# RFM232_V02.net
KiCad netlist of a schematic drawn in Altium Designer
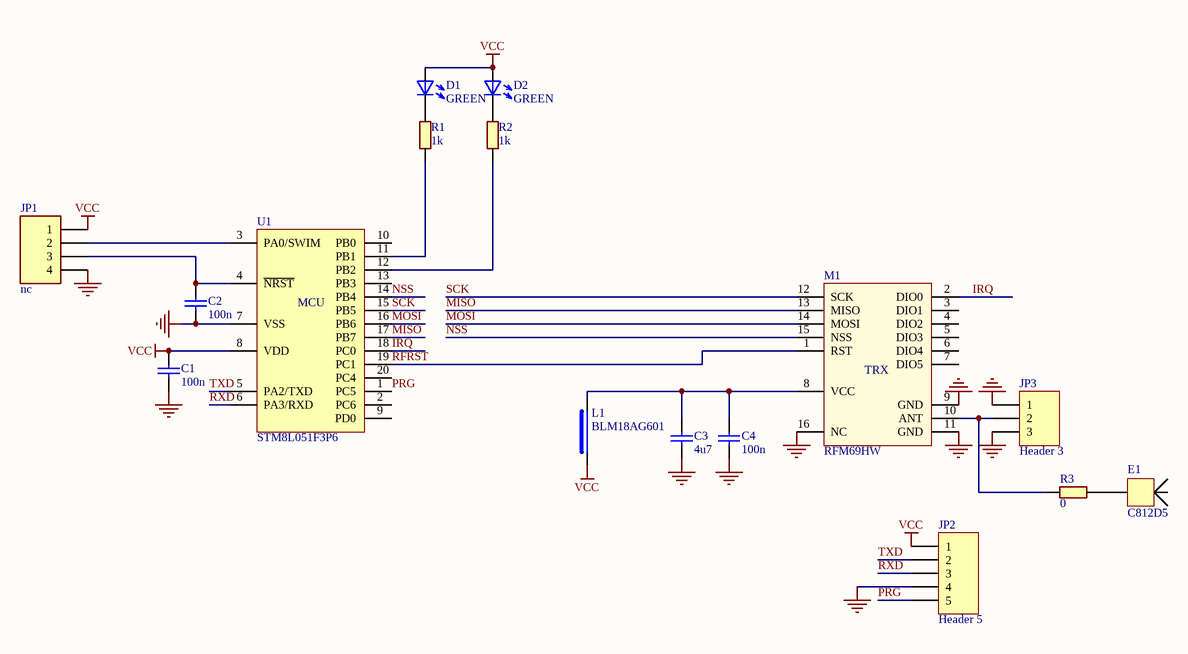
[diagram p0: RFM232_V02.SchDoc]

(export (version "E")
  (design (tool "Eeschema 10.0.6"))
  (components
    (comp (ref "C1") (value "100n") (footprint "CAPC1608X08N") (libsource (lib "Discrete") (part "CAPN")))
    (comp (ref "C2") (value "100n") (footprint "CAPC1608X08N") (libsource (lib "Discrete") (part "CAPN")))
    (comp (ref "C3") (value "4u7") (footprint "CAPC2012X11N") (libsource (lib "Discrete") (part "CAPN")))
    (comp (ref "C4") (value "100n") (footprint "CAPC1608X08N") (libsource (lib "Discrete") (part "CAPN")))
    (comp (ref "D1")
      (value "GREEN")
      (footprint "LEDC200X125X80L40N")
      (libsource (lib "Discrete") (part "DLED"))
    )
    (comp (ref "D2")
      (value "GREEN")
      (footprint "LEDC200X125X80L40N")
      (libsource (lib "Discrete") (part "DLED"))
    )
    (comp (ref "E1") (value "C812D5") (footprint "C812D5") (libsource (lib "RFUART") (part "C812D5")))
    (comp (ref "JP1")
      (value "nc")
      (footprint "HDRV4W70P254_4X1_889X254H754")
      (description "4 Pin Header 2,0 mm, 1x04")
      (libsource (lib "e4") (part "HEADER 4"))
    )
    (comp (ref "JP2")
      (value "Header 5")
      (footprint "HDRV5W70P254_5X1_1143X254H754")
      (description "Header, 5-Pin")
      (fields (field (name "PUBLISHER") "Altium Limited"))
      (libsource (lib "Miscellaneous Connectors") (part "Header 5"))
    )
    (comp (ref "JP3")
      (value "Header 3")
      (footprint "HDRV3W70P254_3X1_635X254H754")
      (description "Header, 3-Pin")
      (fields (field (name "PUBLISHER") "Altium Limited"))
      (libsource (lib "Miscellaneous Connectors") (part "Header 3"))
    )
    (comp (ref "L1")
      (value "BLM18AG601")
      (footprint "INDC1608X10N")
      (libsource (lib "Discrete") (part "SUPRESOR"))
    )
    (comp (ref "M1")
      (value "RFM69HW")
      (footprint "LGA16_RFM69")
      (libsource (lib "CLAP_M505_WL_BP_V22") (part "RFM69HW_V13_2"))
    )
    (comp (ref "R1") (value "1k") (footprint "RESC1608X06N") (libsource (lib "") (part "RES_1")))
    (comp (ref "R2") (value "1k") (footprint "RESC1608X06N") (libsource (lib "") (part "RES_1")))
    (comp (ref "R3") (value "0") (footprint "RESC2012X07N") (libsource (lib "Discrete") (part "RES")))
    (comp (ref "U1")
      (value "STM8L051F3P6")
      (footprint "TSOP65P640X110-20N")
      (libsource (lib "reedswitch_stm8l") (part "STM8L051F3P6"))
    )
  )
  (nets
    (net (code "1") (name "/IRQ") (class "Default")
      (node (ref "M1") (pin "2") (pinfunction "DIO0_2") (pintype "passive"))
      (node (ref "U1") (pin "18") (pinfunction "PC0_18") (pintype "passive"))
    )
    (net (code "2") (name "/MISO") (class "Default")
      (node (ref "M1") (pin "13") (pinfunction "MISO_13") (pintype "passive"))
      (node (ref "U1") (pin "17") (pinfunction "PB7_17") (pintype "passive"))
    )
    (net (code "3") (name "/MOSI") (class "Default")
      (node (ref "M1") (pin "14") (pinfunction "MOSI_14") (pintype "passive"))
      (node (ref "U1") (pin "16") (pinfunction "PB6_16") (pintype "passive"))
    )
    (net (code "4") (name "/NSS") (class "Default")
      (node (ref "M1") (pin "15") (pinfunction "NSS_15") (pintype "passive"))
      (node (ref "U1") (pin "14") (pinfunction "PB4_14") (pintype "passive"))
    )
    (net (code "5") (name "/PRG") (class "Default")
      (node (ref "JP2") (pin "5") (pinfunction "5_5") (pintype "passive"))
      (node (ref "U1") (pin "1") (pinfunction "PC5_1") (pintype "passive"))
    )
    (net (code "6") (name "/RFRST") (class "Default")
      (node (ref "M1") (pin "1") (pinfunction "RST_1") (pintype "passive"))
      (node (ref "U1") (pin "19") (pinfunction "PC1_19") (pintype "passive"))
    )
    (net (code "7") (name "/RXD") (class "Default")
      (node (ref "JP2") (pin "3") (pinfunction "3_3") (pintype "passive"))
      (node (ref "U1") (pin "6") (pinfunction "PA3/RXD_6") (pintype "passive"))
    )
    (net (code "8") (name "/SCK") (class "Default")
      (node (ref "M1") (pin "12") (pinfunction "SCK_12") (pintype "passive"))
      (node (ref "U1") (pin "15") (pinfunction "PB5_15") (pintype "passive"))
    )
    (net (code "9") (name "/TXD") (class "Default")
      (node (ref "JP2") (pin "2") (pinfunction "2_2") (pintype "passive"))
      (node (ref "U1") (pin "5") (pinfunction "PA2/TXD_5") (pintype "passive"))
    )
    (net (code "10") (name "GND") (class "Default")
      (node (ref "C1") (pin "2") (pinfunction "2_2") (pintype "passive"))
      (node (ref "C2") (pin "2") (pinfunction "2_2") (pintype "passive"))
      (node (ref "C3") (pin "2") (pinfunction "2_2") (pintype "passive"))
      (node (ref "C4") (pin "2") (pinfunction "2_2") (pintype "passive"))
      (node (ref "JP1") (pin "4") (pinfunction "4_4") (pintype "passive"))
      (node (ref "JP2") (pin "4") (pinfunction "4_4") (pintype "passive"))
      (node (ref "JP3") (pin "1") (pinfunction "1_1") (pintype "passive"))
      (node (ref "JP3") (pin "3") (pinfunction "3_3") (pintype "passive"))
      (node (ref "M1") (pin "11") (pinfunction "GND_11") (pintype "passive"))
      (node (ref "M1") (pin "16") (pinfunction "NC_16") (pintype "passive"))
      (node (ref "M1") (pin "9") (pinfunction "GND_9") (pintype "passive"))
      (node (ref "U1") (pin "7") (pinfunction "VSS_7") (pintype "passive"))
    )
    (net (code "11") (name "Net-(D1-2)") (class "Default")
      (node (ref "D1") (pin "K") (pinfunction "2_K") (pintype "passive"))
      (node (ref "R1") (pin "1") (pinfunction "1_1") (pintype "passive"))
    )
    (net (code "12") (name "Net-(D2-2)") (class "Default")
      (node (ref "D2") (pin "K") (pinfunction "2_K") (pintype "passive"))
      (node (ref "R2") (pin "1") (pinfunction "1_1") (pintype "passive"))
    )
    (net (code "13") (name "Net-(E1-IN)") (class "Default")
      (node (ref "E1") (pin "1") (pinfunction "IN_1") (pintype "passive"))
      (node (ref "R3") (pin "2") (pinfunction "2_2") (pintype "passive"))
    )
    (net (code "14") (name "Net-(M1-ANT)") (class "Default")
      (node (ref "JP3") (pin "2") (pinfunction "2_2") (pintype "passive"))
      (node (ref "M1") (pin "10") (pinfunction "ANT_10") (pintype "passive"))
      (node (ref "R3") (pin "1") (pinfunction "1_1") (pintype "passive"))
    )
    (net (code "15") (name "Net-(M1-VCC)") (class "Default")
      (node (ref "C3") (pin "1") (pinfunction "1_1") (pintype "passive"))
      (node (ref "C4") (pin "1") (pinfunction "1_1") (pintype "passive"))
      (node (ref "L1") (pin "2") (pinfunction "2_2") (pintype "passive"))
      (node (ref "M1") (pin "8") (pinfunction "VCC_8") (pintype "passive"))
    )
    (net (code "16") (name "Net-(U1-PA0{slash}SWIM)") (class "Default")
      (node (ref "JP1") (pin "2") (pinfunction "2_2") (pintype "passive"))
      (node (ref "U1") (pin "3") (pinfunction "PA0/SWIM_3") (pintype "passive"))
    )
    (net (code "17") (name "Net-(U1-PB1)") (class "Default")
      (node (ref "R1") (pin "2") (pinfunction "2_2") (pintype "passive"))
      (node (ref "U1") (pin "11") (pinfunction "PB1_11") (pintype "passive"))
    )
    (net (code "18") (name "Net-(U1-PB2)") (class "Default")
      (node (ref "R2") (pin "2") (pinfunction "2_2") (pintype "passive"))
      (node (ref "U1") (pin "12") (pinfunction "PB2_12") (pintype "passive"))
    )
    (net (code "19") (name "Net-(U1-~{NRST})") (class "Default")
      (node (ref "C2") (pin "1") (pinfunction "1_1") (pintype "passive"))
      (node (ref "JP1") (pin "3") (pinfunction "3_3") (pintype "passive"))
      (node (ref "U1") (pin "4") (pinfunction "~{NRST}_4") (pintype "passive"))
    )
    (net (code "20") (name "VCC") (class "Default")
      (node (ref "C1") (pin "1") (pinfunction "1_1") (pintype "passive"))
      (node (ref "D1") (pin "A") (pinfunction "1_A") (pintype "passive"))
      (node (ref "D2") (pin "A") (pinfunction "1_A") (pintype "passive"))
      (node (ref "JP1") (pin "1") (pinfunction "1_1") (pintype "passive"))
      (node (ref "JP2") (pin "1") (pinfunction "1_1") (pintype "passive"))
      (node (ref "L1") (pin "1") (pinfunction "1_1") (pintype "passive"))
      (node (ref "U1") (pin "8") (pinfunction "VDD_8") (pintype "passive"))
    )
    (net (code "21") (name "unconnected-(M1-DIO1-Pad3)") (class "Default")
      (node (ref "M1") (pin "3") (pinfunction "DIO1_3") (pintype "passive"))
    )
    (net (code "22") (name "unconnected-(M1-DIO2-Pad4)") (class "Default")
      (node (ref "M1") (pin "4") (pinfunction "DIO2_4") (pintype "passive"))
    )
    (net (code "23") (name "unconnected-(M1-DIO3-Pad5)") (class "Default")
      (node (ref "M1") (pin "5") (pinfunction "DIO3_5") (pintype "passive"))
    )
    (net (code "24") (name "unconnected-(M1-DIO4-Pad6)") (class "Default")
      (node (ref "M1") (pin "6") (pinfunction "DIO4_6") (pintype "passive"))
    )
    (net (code "25") (name "unconnected-(M1-DIO5-Pad7)") (class "Default")
      (node (ref "M1") (pin "7") (pinfunction "DIO5_7") (pintype "passive"))
    )
    (net (code "26") (name "unconnected-(U1-PB0-Pad10)") (class "Default")
      (node (ref "U1") (pin "10") (pinfunction "PB0_10") (pintype "passive"))
    )
    (net (code "27") (name "unconnected-(U1-PB3-Pad13)") (class "Default")
      (node (ref "U1") (pin "13") (pinfunction "PB3_13") (pintype "passive"))
    )
    (net (code "28") (name "unconnected-(U1-PC4-Pad20)") (class "Default")
      (node (ref "U1") (pin "20") (pinfunction "PC4_20") (pintype "passive"))
    )
    (net (code "29") (name "unconnected-(U1-PC6-Pad2)") (class "Default")
      (node (ref "U1") (pin "2") (pinfunction "PC6_2") (pintype "passive"))
    )
    (net (code "30") (name "unconnected-(U1-PD0-Pad9)") (class "Default")
      (node (ref "U1") (pin "9") (pinfunction "PD0_9") (pintype "passive"))
    )
  )
)
